# osc.net
KiCad netlist of a schematic drawn in EAGLE
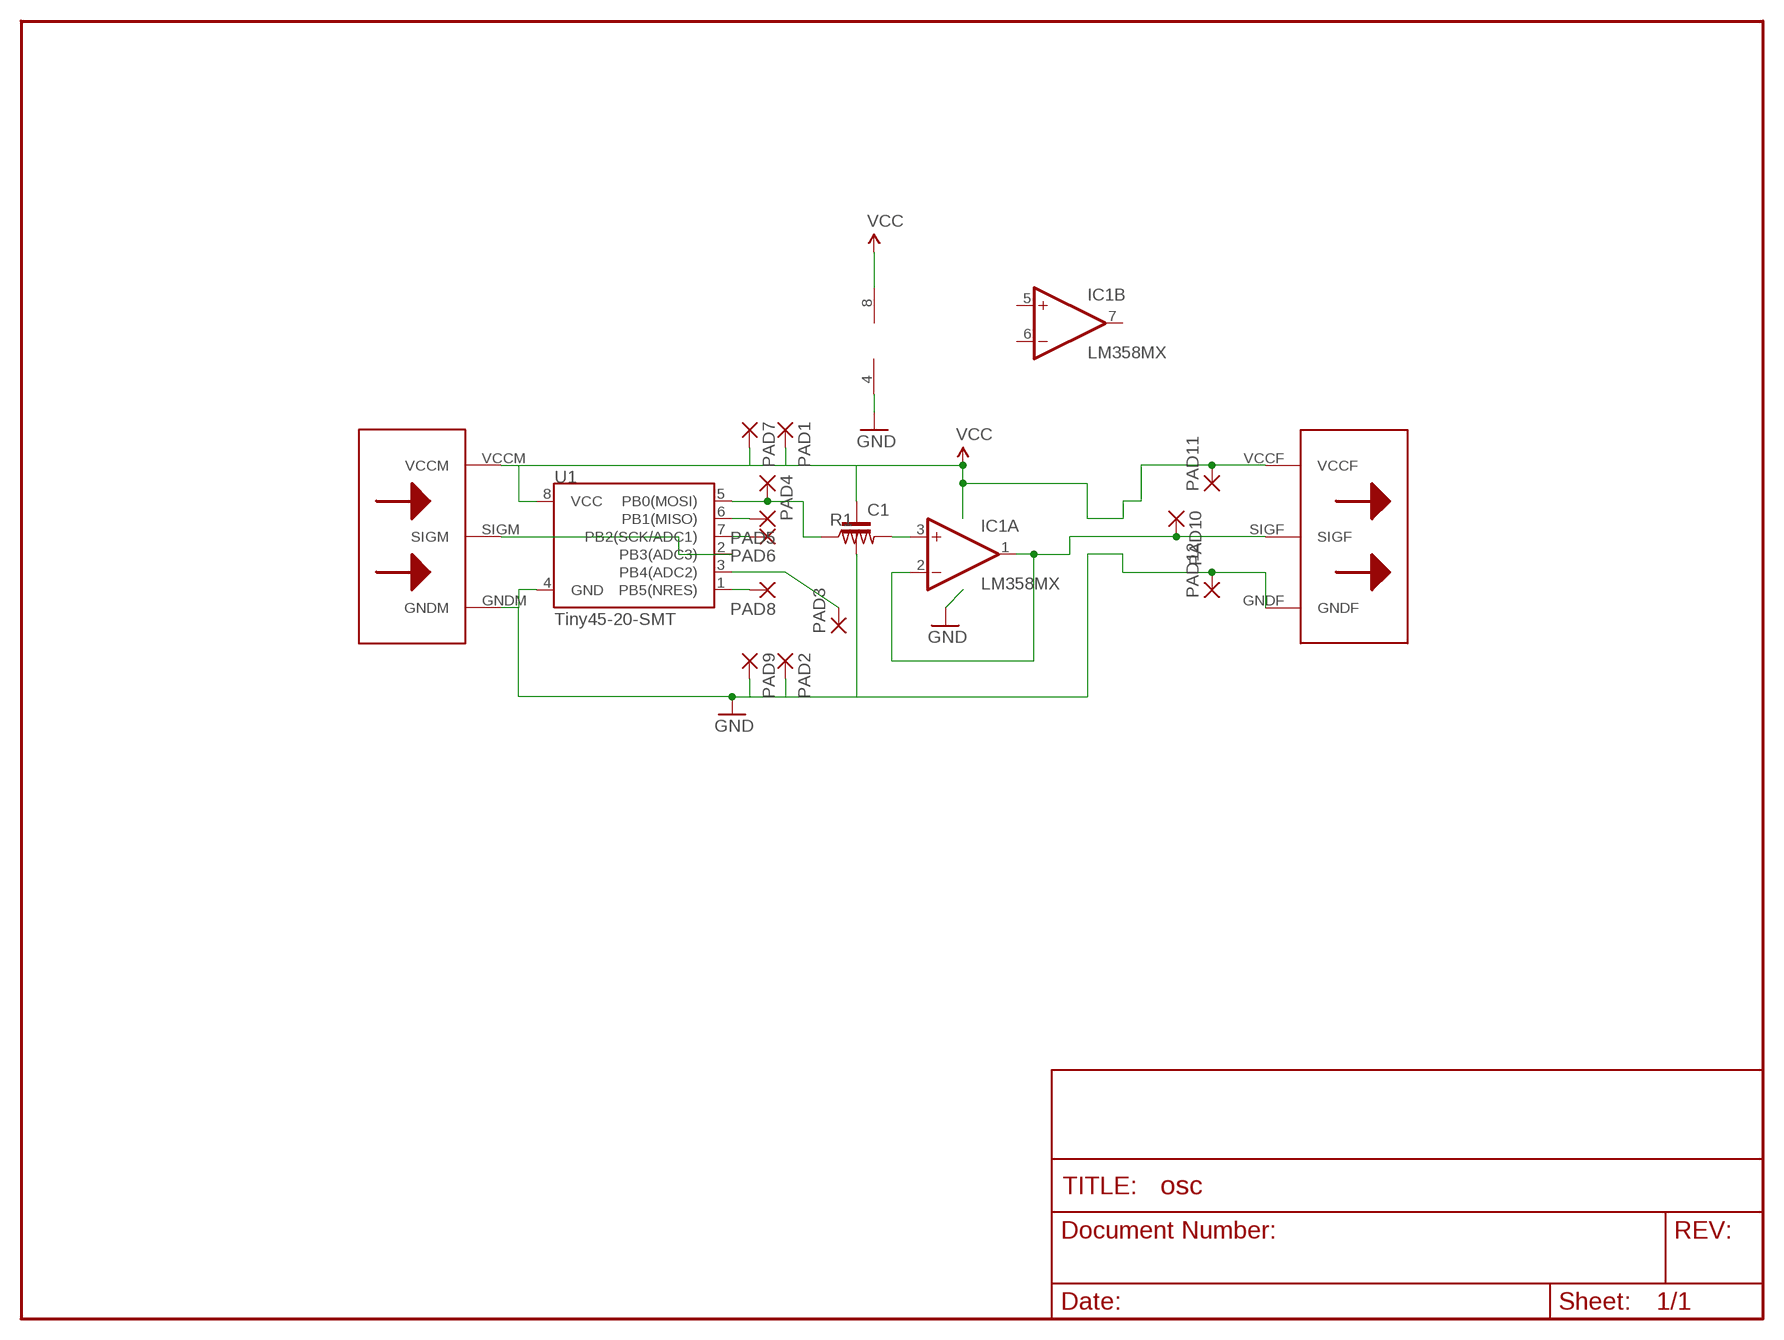
[diagram p0: schematic, sheet 1]

(export (version "E")
  (design (tool "Eeschema 10.0.6"))
  (components
    (comp (ref "C1")
      (value "C-EUC1206K")
      (footprint "eagle-import:C1206K")
      (libsource (lib "eagle-import") (part "C-EUC1206K"))
    )
    (comp (ref "IC1")
      (value "LM358MX")
      (footprint "eagle-import:SO08")
      (libsource (lib "eagle-import") (part "LM358MX"))
    )
    (comp (ref "PAD1")
      (value "SMD2")
      (footprint "eagle-import:SMD1,27-2,54")
      (libsource (lib "eagle-import") (part "SMD2"))
    )
    (comp (ref "PAD2")
      (value "SMD2")
      (footprint "eagle-import:SMD1,27-2,54")
      (libsource (lib "eagle-import") (part "SMD2"))
    )
    (comp (ref "PAD3")
      (value "SMD2")
      (footprint "eagle-import:SMD1,27-2,54")
      (libsource (lib "eagle-import") (part "SMD2"))
    )
    (comp (ref "PAD4")
      (value "SMD2")
      (footprint "eagle-import:SMD1,27-2,54")
      (libsource (lib "eagle-import") (part "SMD2"))
    )
    (comp (ref "PAD5")
      (value "SMD2")
      (footprint "eagle-import:SMD1,27-2,54")
      (libsource (lib "eagle-import") (part "SMD2"))
    )
    (comp (ref "PAD6")
      (value "SMD2")
      (footprint "eagle-import:SMD1,27-2,54")
      (libsource (lib "eagle-import") (part "SMD2"))
    )
    (comp (ref "PAD7")
      (value "SMD2")
      (footprint "eagle-import:SMD1,27-2,54")
      (libsource (lib "eagle-import") (part "SMD2"))
    )
    (comp (ref "PAD8")
      (value "SMD2")
      (footprint "eagle-import:SMD1,27-2,54")
      (libsource (lib "eagle-import") (part "SMD2"))
    )
    (comp (ref "PAD9")
      (value "SMD2")
      (footprint "eagle-import:SMD1,27-2,54")
      (libsource (lib "eagle-import") (part "SMD2"))
    )
    (comp (ref "PAD10")
      (value "SMD2")
      (footprint "eagle-import:SMD1,27-2,54")
      (libsource (lib "eagle-import") (part "SMD2"))
    )
    (comp (ref "PAD11")
      (value "SMD2")
      (footprint "eagle-import:SMD1,27-2,54")
      (libsource (lib "eagle-import") (part "SMD2"))
    )
    (comp (ref "PAD12")
      (value "SMD2")
      (footprint "eagle-import:SMD1,27-2,54")
      (libsource (lib "eagle-import") (part "SMD2"))
    )
    (comp (ref "R1")
      (value "R-US_R0805")
      (footprint "eagle-import:R0805")
      (libsource (lib "eagle-import") (part "R-US_R0805"))
    )
    (comp (ref "U$6")
      (value "BIGBIT")
      (footprint "eagle-import:BIGBIT")
      (libsource (lib "eagle-import") (part "BIGBIT"))
    )
    (comp (ref "U1")
      (value "Tiny45-20-SMT")
      (footprint "eagle-import:SO08-EIAJ")
      (libsource (lib "eagle-import") (part "ATTINY45TINY45-20-SMT"))
    )
  )
  (nets
    (net (code "1") (name "GND") (class "Default")
      (node (ref "C1") (pin "2") (pinfunction "2_2") (pintype "passive"))
      (node (ref "IC1") (pin "4") (pinfunction "V-_4") (pintype "power_in"))
      (node (ref "PAD12") (pin "1") (pinfunction "P_1") (pintype "passive"))
      (node (ref "PAD2") (pin "1") (pinfunction "P_1") (pintype "passive"))
      (node (ref "PAD9") (pin "1") (pinfunction "P_1") (pintype "passive"))
      (node (ref "U$6") (pin "GNDF") (pinfunction "GNDF_GNDF") (pintype "bidirectional"))
      (node (ref "U$6") (pin "GNDM") (pinfunction "GNDM_GNDM") (pintype "bidirectional"))
      (node (ref "U1") (pin "4") (pinfunction "GND_4") (pintype "bidirectional"))
    )
    (net (code "2") (name "Net-(IC1A-+IN)") (class "Default")
      (node (ref "IC1") (pin "3") (pinfunction "+IN_3") (pintype "input"))
      (node (ref "R1") (pin "2") (pinfunction "2_2") (pintype "passive"))
    )
    (net (code "3") (name "Net-(IC1A--IN)") (class "Default")
      (node (ref "IC1") (pin "1") (pinfunction "OUT_1") (pintype "output"))
      (node (ref "IC1") (pin "2") (pinfunction "-IN_2") (pintype "input"))
      (node (ref "PAD10") (pin "1") (pinfunction "P_1") (pintype "passive"))
      (node (ref "U$6") (pin "SIGF") (pinfunction "SIGF_SIGF") (pintype "bidirectional"))
    )
    (net (code "4") (name "Net-(PAD3-P)") (class "Default")
      (node (ref "PAD3") (pin "1") (pinfunction "P_1") (pintype "passive"))
      (node (ref "U1") (pin "3") (pinfunction "PB4(ADC2)_3") (pintype "bidirectional"))
    )
    (net (code "5") (name "Net-(PAD4-P)") (class "Default")
      (node (ref "PAD4") (pin "1") (pinfunction "P_1") (pintype "passive"))
      (node (ref "R1") (pin "1") (pinfunction "1_1") (pintype "passive"))
      (node (ref "U1") (pin "5") (pinfunction "PB0(MOSI)_5") (pintype "bidirectional"))
    )
    (net (code "6") (name "Net-(PAD5-P)") (class "Default")
      (node (ref "PAD5") (pin "1") (pinfunction "P_1") (pintype "passive"))
      (node (ref "U1") (pin "6") (pinfunction "PB1(MISO)_6") (pintype "bidirectional"))
    )
    (net (code "7") (name "Net-(PAD6-P)") (class "Default")
      (node (ref "PAD6") (pin "1") (pinfunction "P_1") (pintype "passive"))
      (node (ref "U1") (pin "7") (pinfunction "PB2(SCK/ADC1)_7") (pintype "bidirectional"))
    )
    (net (code "8") (name "Net-(PAD8-P)") (class "Default")
      (node (ref "PAD8") (pin "1") (pinfunction "P_1") (pintype "passive"))
      (node (ref "U1") (pin "1") (pinfunction "PB5(NRES)_1") (pintype "bidirectional"))
    )
    (net (code "9") (name "Net-(U1-PB3(ADC3))") (class "Default")
      (node (ref "U$6") (pin "SIGM") (pinfunction "SIGM_SIGM") (pintype "bidirectional"))
      (node (ref "U1") (pin "2") (pinfunction "PB3(ADC3)_2") (pintype "bidirectional"))
    )
    (net (code "10") (name "VCC") (class "Default")
      (node (ref "C1") (pin "1") (pinfunction "1_1") (pintype "passive"))
      (node (ref "IC1") (pin "8") (pinfunction "V+_8") (pintype "power_in"))
      (node (ref "PAD1") (pin "1") (pinfunction "P_1") (pintype "passive"))
      (node (ref "PAD11") (pin "1") (pinfunction "P_1") (pintype "passive"))
      (node (ref "PAD7") (pin "1") (pinfunction "P_1") (pintype "passive"))
      (node (ref "U$6") (pin "VCCF") (pinfunction "VCCF_VCCF") (pintype "bidirectional"))
      (node (ref "U$6") (pin "VCCM") (pinfunction "VCCM_VCCM") (pintype "bidirectional"))
      (node (ref "U1") (pin "8") (pinfunction "VCC_8") (pintype "bidirectional"))
    )
    (net (code "11") (name "unconnected-(IC1B-+IN-Pad5)") (class "Default")
      (node (ref "IC1") (pin "5") (pinfunction "+IN_5") (pintype "input"))
    )
    (net (code "12") (name "unconnected-(IC1B--IN-Pad6)") (class "Default")
      (node (ref "IC1") (pin "6") (pinfunction "-IN_6") (pintype "input"))
    )
    (net (code "13") (name "unconnected-(IC1B-OUT-Pad7)") (class "Default")
      (node (ref "IC1") (pin "7") (pinfunction "OUT_7") (pintype "output"))
    )
  )
)
